# 14_seg_0_5_8_digit.net
KiCad netlist of a schematic drawn in EAGLE
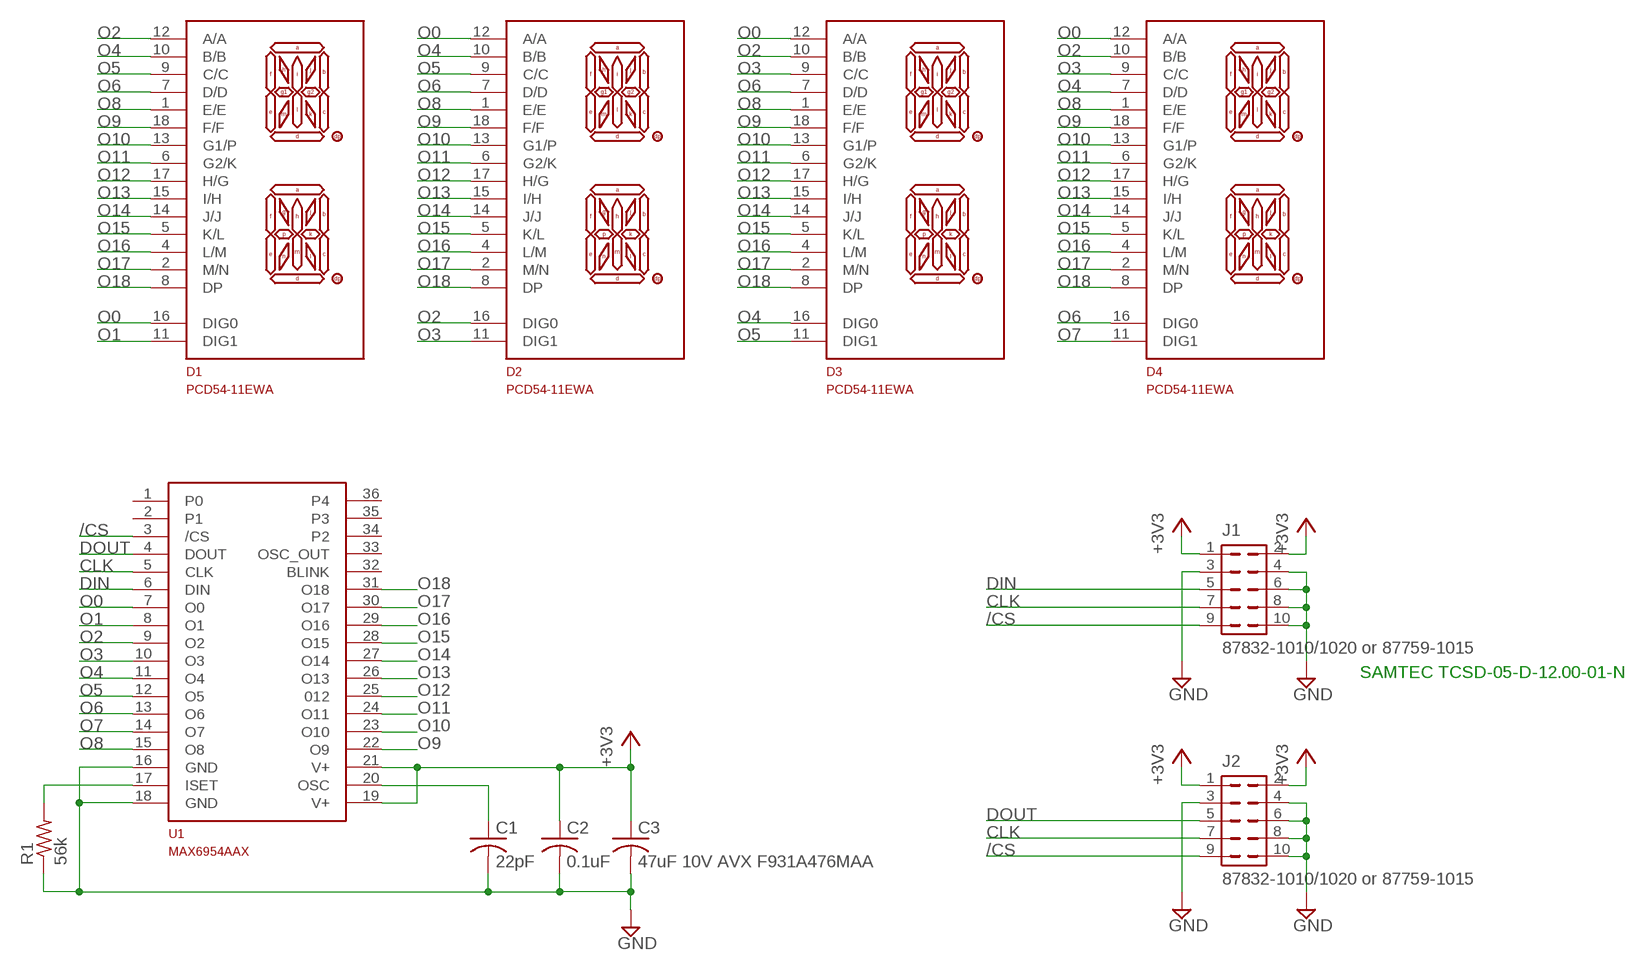
[diagram p0: schematic, sheet 1]

(export (version "E")
  (design (tool "Eeschema 10.0.6"))
  (components
    (comp (ref "C1")
      (value "22pF")
      (footprint "eagle-import:C1206")
      (libsource (lib "eagle-import") (part "C-USC1206"))
    )
    (comp (ref "C2")
      (value "0.1uF")
      (footprint "eagle-import:C1206")
      (libsource (lib "eagle-import") (part "C-USC1206"))
    )
    (comp (ref "C3")
      (value "47uF 10V AVX F931A476MAA")
      (footprint "eagle-import:C1206")
      (libsource (lib "eagle-import") (part "C-USC1206"))
    )
    (comp (ref "D1")
      (value "PCD54-11EWA")
      (footprint "eagle-import:PDC54-11")
      (libsource (lib "eagle-import") (part "PCD54-11EWA"))
    )
    (comp (ref "D2")
      (value "PCD54-11EWA")
      (footprint "eagle-import:PDC54-11")
      (libsource (lib "eagle-import") (part "PCD54-11EWA"))
    )
    (comp (ref "D3")
      (value "PCD54-11EWA")
      (footprint "eagle-import:PDC54-11")
      (libsource (lib "eagle-import") (part "PCD54-11EWA"))
    )
    (comp (ref "D4")
      (value "PCD54-11EWA")
      (footprint "eagle-import:PDC54-11")
      (libsource (lib "eagle-import") (part "PCD54-11EWA"))
    )
    (comp (ref "J1")
      (value "87832-1010/1020 or 87759-1015")
      (footprint "eagle-import:87832-10")
      (libsource (lib "eagle-import") (part "87832-10"))
    )
    (comp (ref "J2")
      (value "87832-1010/1020 or 87759-1015")
      (footprint "eagle-import:87832-10")
      (libsource (lib "eagle-import") (part "87832-10"))
    )
    (comp (ref "R1")
      (value "56k")
      (footprint "eagle-import:R1206")
      (libsource (lib "eagle-import") (part "R-US_R1206"))
    )
    (comp (ref "U1")
      (value "MAX6954AAX")
      (footprint "eagle-import:MAXIM-0.8-SSOP36")
      (libsource (lib "eagle-import") (part "MAX6954AAX"))
    )
  )
  (nets
    (net (code "1") (name "+3V3") (class "Default")
      (node (ref "C2") (pin "1") (pinfunction "1_1") (pintype "passive"))
      (node (ref "C3") (pin "1") (pinfunction "1_1") (pintype "passive"))
      (node (ref "J1") (pin "1") (pinfunction "1_1") (pintype "passive"))
      (node (ref "J1") (pin "2") (pinfunction "2_2") (pintype "passive"))
      (node (ref "J2") (pin "1") (pinfunction "1_1") (pintype "passive"))
      (node (ref "J2") (pin "2") (pinfunction "2_2") (pintype "passive"))
      (node (ref "U1") (pin "19") (pinfunction "V+_19") (pintype "bidirectional"))
      (node (ref "U1") (pin "21") (pinfunction "V+_21") (pintype "bidirectional"))
    )
    (net (code "2") (name "/CLK") (class "Default")
      (node (ref "J1") (pin "7") (pinfunction "7_7") (pintype "passive"))
      (node (ref "J2") (pin "7") (pinfunction "7_7") (pintype "passive"))
      (node (ref "U1") (pin "5") (pinfunction "CLK_5") (pintype "bidirectional"))
    )
    (net (code "3") (name "/DIN") (class "Default")
      (node (ref "J1") (pin "5") (pinfunction "5_5") (pintype "passive"))
      (node (ref "U1") (pin "6") (pinfunction "DIN_6") (pintype "bidirectional"))
    )
    (net (code "4") (name "/DOUT") (class "Default")
      (node (ref "J2") (pin "5") (pinfunction "5_5") (pintype "passive"))
      (node (ref "U1") (pin "4") (pinfunction "DOUT_4") (pintype "bidirectional"))
    )
    (net (code "5") (name "/O0") (class "Default")
      (node (ref "D1") (pin "16") (pinfunction "DIG0_16") (pintype "bidirectional"))
      (node (ref "D2") (pin "12") (pinfunction "A/A_12") (pintype "bidirectional"))
      (node (ref "D3") (pin "12") (pinfunction "A/A_12") (pintype "bidirectional"))
      (node (ref "D4") (pin "12") (pinfunction "A/A_12") (pintype "bidirectional"))
      (node (ref "U1") (pin "7") (pinfunction "O0_7") (pintype "bidirectional"))
    )
    (net (code "6") (name "/O1") (class "Default")
      (node (ref "D1") (pin "11") (pinfunction "DIG1_11") (pintype "bidirectional"))
      (node (ref "U1") (pin "8") (pinfunction "O1_8") (pintype "bidirectional"))
    )
    (net (code "7") (name "/O2") (class "Default")
      (node (ref "D1") (pin "12") (pinfunction "A/A_12") (pintype "bidirectional"))
      (node (ref "D2") (pin "16") (pinfunction "DIG0_16") (pintype "bidirectional"))
      (node (ref "D3") (pin "10") (pinfunction "B/B_10") (pintype "bidirectional"))
      (node (ref "D4") (pin "10") (pinfunction "B/B_10") (pintype "bidirectional"))
      (node (ref "U1") (pin "9") (pinfunction "O2_9") (pintype "bidirectional"))
    )
    (net (code "8") (name "/O3") (class "Default")
      (node (ref "D2") (pin "11") (pinfunction "DIG1_11") (pintype "bidirectional"))
      (node (ref "D3") (pin "9") (pinfunction "C/C_9") (pintype "bidirectional"))
      (node (ref "D4") (pin "9") (pinfunction "C/C_9") (pintype "bidirectional"))
      (node (ref "U1") (pin "10") (pinfunction "O3_10") (pintype "bidirectional"))
    )
    (net (code "9") (name "/O4") (class "Default")
      (node (ref "D1") (pin "10") (pinfunction "B/B_10") (pintype "bidirectional"))
      (node (ref "D2") (pin "10") (pinfunction "B/B_10") (pintype "bidirectional"))
      (node (ref "D3") (pin "16") (pinfunction "DIG0_16") (pintype "bidirectional"))
      (node (ref "D4") (pin "7") (pinfunction "D/D_7") (pintype "bidirectional"))
      (node (ref "U1") (pin "11") (pinfunction "O4_11") (pintype "bidirectional"))
    )
    (net (code "10") (name "/O5") (class "Default")
      (node (ref "D1") (pin "9") (pinfunction "C/C_9") (pintype "bidirectional"))
      (node (ref "D2") (pin "9") (pinfunction "C/C_9") (pintype "bidirectional"))
      (node (ref "D3") (pin "11") (pinfunction "DIG1_11") (pintype "bidirectional"))
      (node (ref "U1") (pin "12") (pinfunction "O5_12") (pintype "bidirectional"))
    )
    (net (code "11") (name "/O6") (class "Default")
      (node (ref "D1") (pin "7") (pinfunction "D/D_7") (pintype "bidirectional"))
      (node (ref "D2") (pin "7") (pinfunction "D/D_7") (pintype "bidirectional"))
      (node (ref "D3") (pin "7") (pinfunction "D/D_7") (pintype "bidirectional"))
      (node (ref "D4") (pin "16") (pinfunction "DIG0_16") (pintype "bidirectional"))
      (node (ref "U1") (pin "13") (pinfunction "O6_13") (pintype "bidirectional"))
    )
    (net (code "12") (name "/O7") (class "Default")
      (node (ref "D4") (pin "11") (pinfunction "DIG1_11") (pintype "bidirectional"))
      (node (ref "U1") (pin "14") (pinfunction "O7_14") (pintype "bidirectional"))
    )
    (net (code "13") (name "/O8") (class "Default")
      (node (ref "D1") (pin "1") (pinfunction "E/E_1") (pintype "bidirectional"))
      (node (ref "D2") (pin "1") (pinfunction "E/E_1") (pintype "bidirectional"))
      (node (ref "D3") (pin "1") (pinfunction "E/E_1") (pintype "bidirectional"))
      (node (ref "D4") (pin "1") (pinfunction "E/E_1") (pintype "bidirectional"))
      (node (ref "U1") (pin "15") (pinfunction "O8_15") (pintype "bidirectional"))
    )
    (net (code "14") (name "/O9") (class "Default")
      (node (ref "D1") (pin "18") (pinfunction "F/F_18") (pintype "bidirectional"))
      (node (ref "D2") (pin "18") (pinfunction "F/F_18") (pintype "bidirectional"))
      (node (ref "D3") (pin "18") (pinfunction "F/F_18") (pintype "bidirectional"))
      (node (ref "D4") (pin "18") (pinfunction "F/F_18") (pintype "bidirectional"))
      (node (ref "U1") (pin "22") (pinfunction "O9_22") (pintype "bidirectional"))
    )
    (net (code "15") (name "/O10") (class "Default")
      (node (ref "D1") (pin "13") (pinfunction "G1/P_13") (pintype "bidirectional"))
      (node (ref "D2") (pin "13") (pinfunction "G1/P_13") (pintype "bidirectional"))
      (node (ref "D3") (pin "13") (pinfunction "G1/P_13") (pintype "bidirectional"))
      (node (ref "D4") (pin "13") (pinfunction "G1/P_13") (pintype "bidirectional"))
      (node (ref "U1") (pin "23") (pinfunction "O10_23") (pintype "bidirectional"))
    )
    (net (code "16") (name "/O11") (class "Default")
      (node (ref "D1") (pin "6") (pinfunction "G2/K_6") (pintype "bidirectional"))
      (node (ref "D2") (pin "6") (pinfunction "G2/K_6") (pintype "bidirectional"))
      (node (ref "D3") (pin "6") (pinfunction "G2/K_6") (pintype "bidirectional"))
      (node (ref "D4") (pin "6") (pinfunction "G2/K_6") (pintype "bidirectional"))
      (node (ref "U1") (pin "24") (pinfunction "O11_24") (pintype "bidirectional"))
    )
    (net (code "17") (name "/O12") (class "Default")
      (node (ref "D1") (pin "17") (pinfunction "H/G_17") (pintype "bidirectional"))
      (node (ref "D2") (pin "17") (pinfunction "H/G_17") (pintype "bidirectional"))
      (node (ref "D3") (pin "17") (pinfunction "H/G_17") (pintype "bidirectional"))
      (node (ref "D4") (pin "17") (pinfunction "H/G_17") (pintype "bidirectional"))
      (node (ref "U1") (pin "25") (pinfunction "012_25") (pintype "bidirectional"))
    )
    (net (code "18") (name "/O13") (class "Default")
      (node (ref "D1") (pin "15") (pinfunction "I/H_15") (pintype "bidirectional"))
      (node (ref "D2") (pin "15") (pinfunction "I/H_15") (pintype "bidirectional"))
      (node (ref "D3") (pin "15") (pinfunction "I/H_15") (pintype "bidirectional"))
      (node (ref "D4") (pin "15") (pinfunction "I/H_15") (pintype "bidirectional"))
      (node (ref "U1") (pin "26") (pinfunction "O13_26") (pintype "bidirectional"))
    )
    (net (code "19") (name "/O14") (class "Default")
      (node (ref "D1") (pin "14") (pinfunction "J/J_14") (pintype "bidirectional"))
      (node (ref "D2") (pin "14") (pinfunction "J/J_14") (pintype "bidirectional"))
      (node (ref "D3") (pin "14") (pinfunction "J/J_14") (pintype "bidirectional"))
      (node (ref "D4") (pin "14") (pinfunction "J/J_14") (pintype "bidirectional"))
      (node (ref "U1") (pin "27") (pinfunction "O14_27") (pintype "bidirectional"))
    )
    (net (code "20") (name "/O15") (class "Default")
      (node (ref "D1") (pin "5") (pinfunction "K/L_5") (pintype "bidirectional"))
      (node (ref "D2") (pin "5") (pinfunction "K/L_5") (pintype "bidirectional"))
      (node (ref "D3") (pin "5") (pinfunction "K/L_5") (pintype "bidirectional"))
      (node (ref "D4") (pin "5") (pinfunction "K/L_5") (pintype "bidirectional"))
      (node (ref "U1") (pin "28") (pinfunction "O15_28") (pintype "bidirectional"))
    )
    (net (code "21") (name "/O16") (class "Default")
      (node (ref "D1") (pin "4") (pinfunction "L/M_4") (pintype "bidirectional"))
      (node (ref "D2") (pin "4") (pinfunction "L/M_4") (pintype "bidirectional"))
      (node (ref "D3") (pin "4") (pinfunction "L/M_4") (pintype "bidirectional"))
      (node (ref "D4") (pin "4") (pinfunction "L/M_4") (pintype "bidirectional"))
      (node (ref "U1") (pin "29") (pinfunction "O16_29") (pintype "bidirectional"))
    )
    (net (code "22") (name "/O17") (class "Default")
      (node (ref "D1") (pin "2") (pinfunction "M/N_2") (pintype "bidirectional"))
      (node (ref "D2") (pin "2") (pinfunction "M/N_2") (pintype "bidirectional"))
      (node (ref "D3") (pin "2") (pinfunction "M/N_2") (pintype "bidirectional"))
      (node (ref "D4") (pin "2") (pinfunction "M/N_2") (pintype "bidirectional"))
      (node (ref "U1") (pin "30") (pinfunction "O17_30") (pintype "bidirectional"))
    )
    (net (code "23") (name "/O18") (class "Default")
      (node (ref "D1") (pin "8") (pinfunction "DP_8") (pintype "bidirectional"))
      (node (ref "D2") (pin "8") (pinfunction "DP_8") (pintype "bidirectional"))
      (node (ref "D3") (pin "8") (pinfunction "DP_8") (pintype "bidirectional"))
      (node (ref "D4") (pin "8") (pinfunction "DP_8") (pintype "bidirectional"))
      (node (ref "U1") (pin "31") (pinfunction "O18_31") (pintype "bidirectional"))
    )
    (net (code "24") (name "/{slash}CS") (class "Default")
      (node (ref "J1") (pin "9") (pinfunction "9_9") (pintype "passive"))
      (node (ref "J2") (pin "9") (pinfunction "9_9") (pintype "passive"))
      (node (ref "U1") (pin "3") (pinfunction "/CS_3") (pintype "bidirectional"))
    )
    (net (code "25") (name "GND") (class "Default")
      (node (ref "C1") (pin "2") (pinfunction "2_2") (pintype "passive"))
      (node (ref "C2") (pin "2") (pinfunction "2_2") (pintype "passive"))
      (node (ref "C3") (pin "2") (pinfunction "2_2") (pintype "passive"))
      (node (ref "J1") (pin "10") (pinfunction "10_10") (pintype "passive"))
      (node (ref "J1") (pin "3") (pinfunction "3_3") (pintype "passive"))
      (node (ref "J1") (pin "4") (pinfunction "4_4") (pintype "passive"))
      (node (ref "J1") (pin "6") (pinfunction "6_6") (pintype "passive"))
      (node (ref "J1") (pin "8") (pinfunction "8_8") (pintype "passive"))
      (node (ref "J2") (pin "10") (pinfunction "10_10") (pintype "passive"))
      (node (ref "J2") (pin "3") (pinfunction "3_3") (pintype "passive"))
      (node (ref "J2") (pin "4") (pinfunction "4_4") (pintype "passive"))
      (node (ref "J2") (pin "6") (pinfunction "6_6") (pintype "passive"))
      (node (ref "J2") (pin "8") (pinfunction "8_8") (pintype "passive"))
      (node (ref "R1") (pin "1") (pinfunction "1_1") (pintype "passive"))
      (node (ref "U1") (pin "16") (pinfunction "GND_16") (pintype "bidirectional"))
      (node (ref "U1") (pin "18") (pinfunction "GND_18") (pintype "bidirectional"))
    )
    (net (code "26") (name "Net-(U1-ISET)") (class "Default")
      (node (ref "R1") (pin "2") (pinfunction "2_2") (pintype "passive"))
      (node (ref "U1") (pin "17") (pinfunction "ISET_17") (pintype "bidirectional"))
    )
    (net (code "27") (name "Net-(U1-OSC)") (class "Default")
      (node (ref "C1") (pin "1") (pinfunction "1_1") (pintype "passive"))
      (node (ref "U1") (pin "20") (pinfunction "OSC_20") (pintype "bidirectional"))
    )
    (net (code "28") (name "unconnected-(U1-BLINK-Pad32)") (class "Default")
      (node (ref "U1") (pin "32") (pinfunction "BLINK_32") (pintype "bidirectional"))
    )
    (net (code "29") (name "unconnected-(U1-OSC_OUT-Pad33)") (class "Default")
      (node (ref "U1") (pin "33") (pinfunction "OSC_OUT_33") (pintype "bidirectional"))
    )
    (net (code "30") (name "unconnected-(U1-P0-Pad1)") (class "Default")
      (node (ref "U1") (pin "1") (pinfunction "P0_1") (pintype "bidirectional"))
    )
    (net (code "31") (name "unconnected-(U1-P1-Pad2)") (class "Default")
      (node (ref "U1") (pin "2") (pinfunction "P1_2") (pintype "bidirectional"))
    )
    (net (code "32") (name "unconnected-(U1-P2-Pad34)") (class "Default")
      (node (ref "U1") (pin "34") (pinfunction "P2_34") (pintype "bidirectional"))
    )
    (net (code "33") (name "unconnected-(U1-P3-Pad35)") (class "Default")
      (node (ref "U1") (pin "35") (pinfunction "P3_35") (pintype "bidirectional"))
    )
    (net (code "34") (name "unconnected-(U1-P4-Pad36)") (class "Default")
      (node (ref "U1") (pin "36") (pinfunction "P4_36") (pintype "bidirectional"))
    )
  )
)
